# Radio_Console-AS_ORDERED_2015-05-06.net
KiCad netlist of a schematic drawn in EAGLE
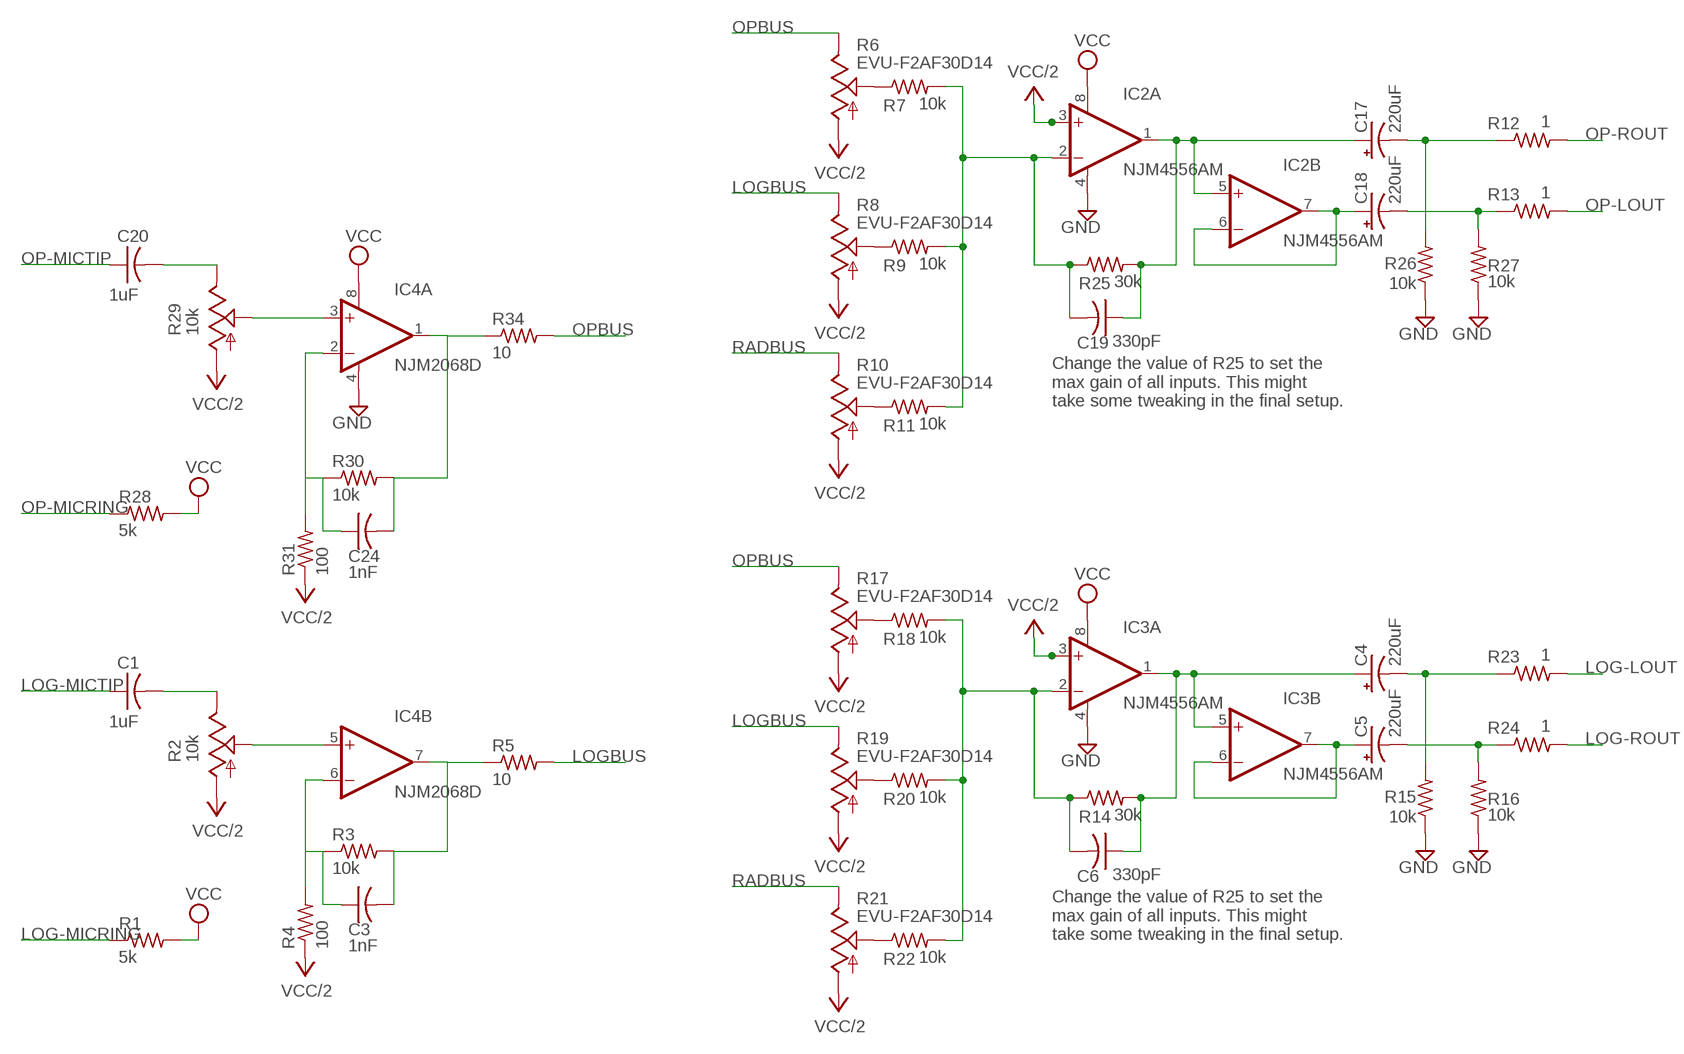
[diagram p0: schematic, sheet 1]
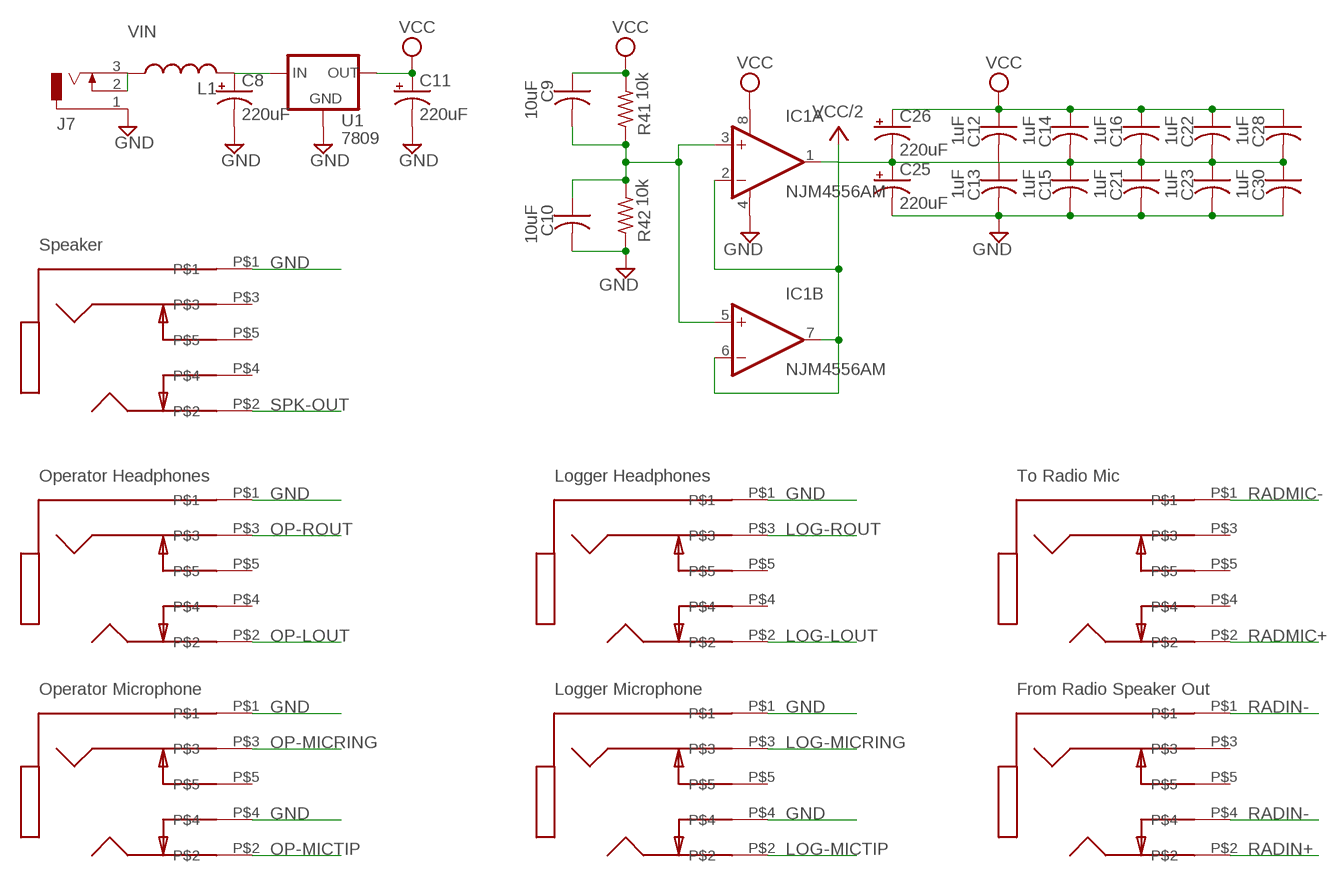
[diagram p1: schematic, sheet 2]
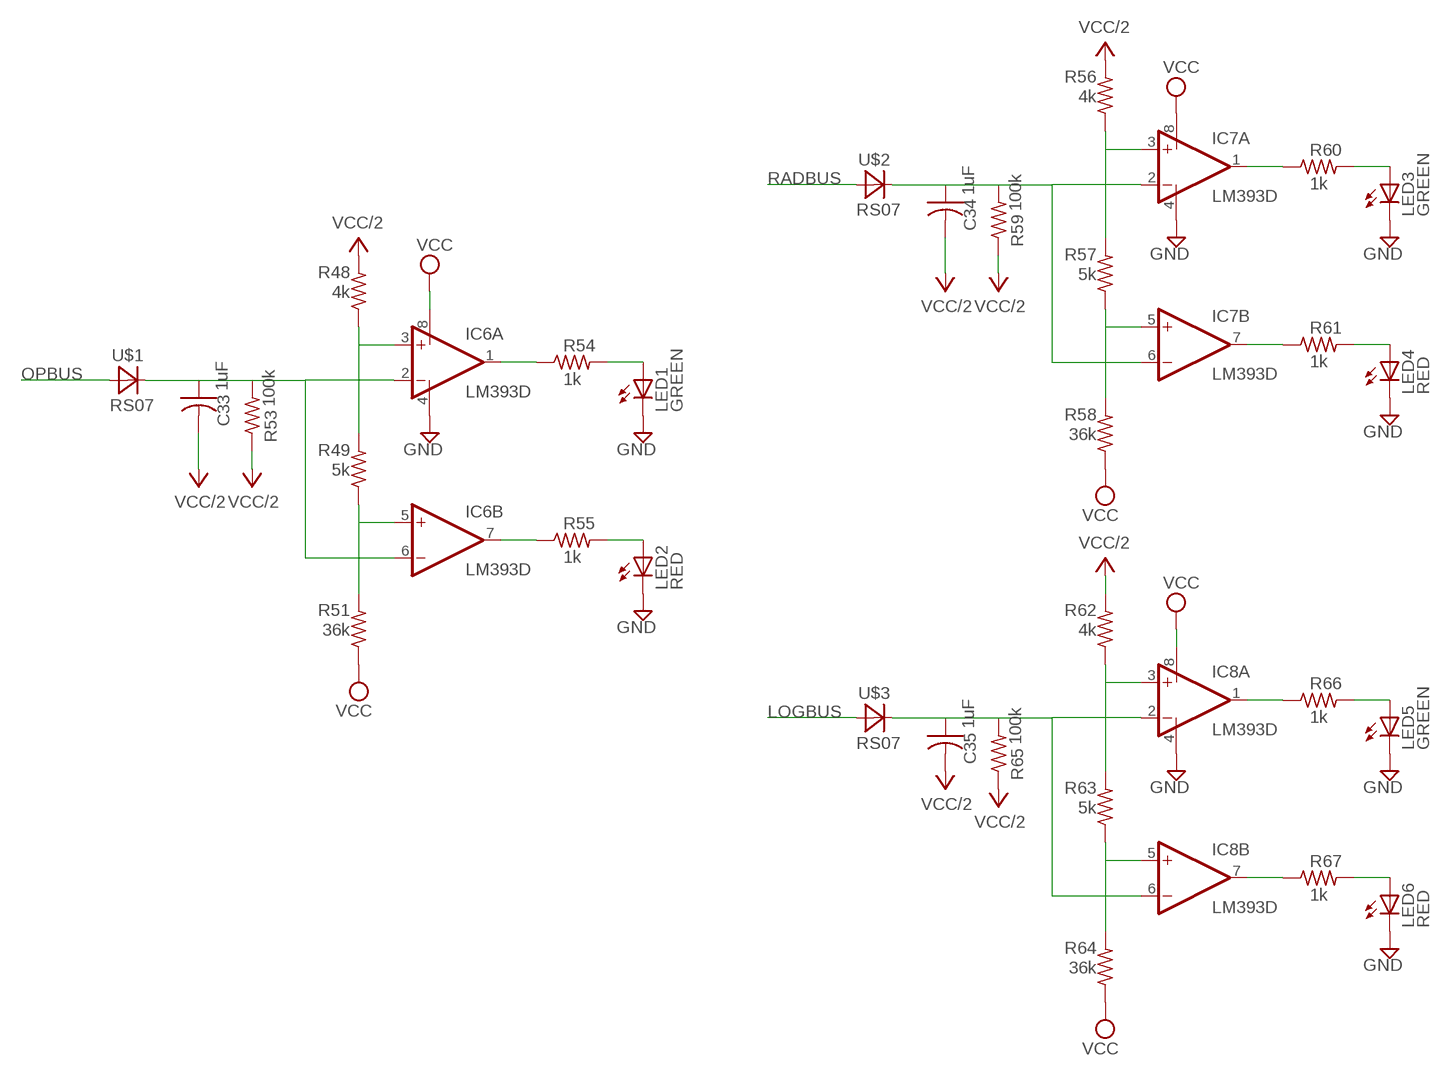
[diagram p2: schematic, sheet 3]
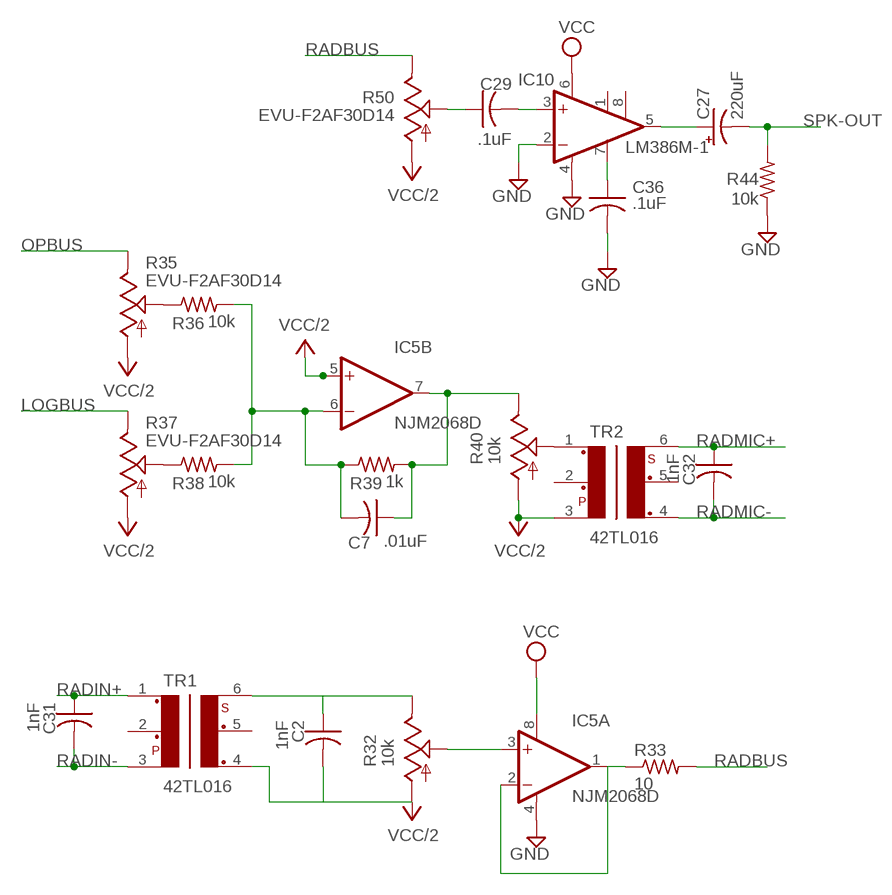
[diagram p3: schematic, sheet 4]

(export (version "E")
  (design (tool "Eeschema 10.0.6"))
  (components
    (comp (ref "C8")
      (value "220uF")
      (footprint "eagle-import:E5-8,5")
      (libsource (lib "eagle-import") (part "CPOL-USE5-8.5"))
    )
    (comp (ref "C9")
      (value "10uF")
      (footprint "eagle-import:C1206")
      (libsource (lib "eagle-import") (part "C-USC1206"))
    )
    (comp (ref "C10")
      (value "10uF")
      (footprint "eagle-import:C1206")
      (libsource (lib "eagle-import") (part "C-USC1206"))
    )
    (comp (ref "C11")
      (value "220uF")
      (footprint "eagle-import:E5-8,5")
      (libsource (lib "eagle-import") (part "CPOL-USE5-8.5"))
    )
    (comp (ref "C12")
      (value "1uF")
      (footprint "eagle-import:C1206")
      (libsource (lib "eagle-import") (part "C-USC1206"))
    )
    (comp (ref "C13")
      (value "1uF")
      (footprint "eagle-import:C1206")
      (libsource (lib "eagle-import") (part "C-USC1206"))
    )
    (comp (ref "C14")
      (value "1uF")
      (footprint "eagle-import:C1206")
      (libsource (lib "eagle-import") (part "C-USC1206"))
    )
    (comp (ref "C15")
      (value "1uF")
      (footprint "eagle-import:C1206")
      (libsource (lib "eagle-import") (part "C-USC1206"))
    )
    (comp (ref "C16")
      (value "1uF")
      (footprint "eagle-import:C1206")
      (libsource (lib "eagle-import") (part "C-USC1206"))
    )
    (comp (ref "C21")
      (value "1uF")
      (footprint "eagle-import:C1206")
      (libsource (lib "eagle-import") (part "C-USC1206"))
    )
    (comp (ref "C22")
      (value "1uF")
      (footprint "eagle-import:C1206")
      (libsource (lib "eagle-import") (part "C-USC1206"))
    )
    (comp (ref "C23")
      (value "1uF")
      (footprint "eagle-import:C1206")
      (libsource (lib "eagle-import") (part "C-USC1206"))
    )
    (comp (ref "C25")
      (value "220uF")
      (footprint "eagle-import:E5-8,5")
      (libsource (lib "eagle-import") (part "CPOL-USE5-8.5"))
    )
    (comp (ref "C26")
      (value "220uF")
      (footprint "eagle-import:E5-8,5")
      (libsource (lib "eagle-import") (part "CPOL-USE5-8.5"))
    )
    (comp (ref "C28")
      (value "1uF")
      (footprint "eagle-import:C1206")
      (libsource (lib "eagle-import") (part "C-USC1206"))
    )
    (comp (ref "C30")
      (value "1uF")
      (footprint "eagle-import:C1206")
      (libsource (lib "eagle-import") (part "C-USC1206"))
    )
    (comp (ref "IC1")
      (value "NJM4556AM")
      (footprint "eagle-import:SO08")
      (fields (field (name "MF") "TEXAS INSTRUMENT CONNECTORS") (field (name "MPN") "OPA2131UJ/2K5"))
      (libsource (lib "eagle-import") (part "OPA2131U"))
    )
    (comp (ref "J1")
      (value "Operator Headphones")
      (footprint "eagle-import:SJ1-353")
      (libsource (lib "eagle-import") (part "SJ1-353"))
    )
    (comp (ref "J2")
      (value "Operator Microphone")
      (footprint "eagle-import:SJ1-353")
      (libsource (lib "eagle-import") (part "SJ1-353"))
    )
    (comp (ref "J3")
      (value "To Radio MIcrophone")
      (footprint "eagle-import:SJ1-353")
      (libsource (lib "eagle-import") (part "SJ1-353"))
    )
    (comp (ref "J4")
      (value "Logger Headphone")
      (footprint "eagle-import:SJ1-353")
      (libsource (lib "eagle-import") (part "SJ1-353"))
    )
    (comp (ref "J5")
      (value "Logger Microphone")
      (footprint "eagle-import:SJ1-353")
      (libsource (lib "eagle-import") (part "SJ1-353"))
    )
    (comp (ref "J6")
      (value "From Radio Speaker Out")
      (footprint "eagle-import:SJ1-353")
      (libsource (lib "eagle-import") (part "SJ1-353"))
    )
    (comp (ref "J7")
      (value "DCJ0303")
      (footprint "eagle-import:DCJ0303")
      (libsource (lib "eagle-import") (part "DCJ0303"))
    )
    (comp (ref "J8")
      (value "Operator Headphones")
      (footprint "eagle-import:SJ1-353")
      (libsource (lib "eagle-import") (part "SJ1-353"))
    )
    (comp (ref "L1")
      (value "L-USL4035M")
      (footprint "eagle-import:L4035M")
      (libsource (lib "eagle-import") (part "L-USL4035M"))
    )
    (comp (ref "R41")
      (value "10k")
      (footprint "eagle-import:R1206")
      (libsource (lib "eagle-import") (part "R-US_R1206"))
    )
    (comp (ref "R42")
      (value "10k")
      (footprint "eagle-import:R1206")
      (libsource (lib "eagle-import") (part "R-US_R1206"))
    )
    (comp (ref "U1")
      (value "7809")
      (footprint "eagle-import:D2PACK")
      (libsource (lib "eagle-import") (part "78XX-TO263"))
    )
    (comp (ref "C33")
      (value "1uF")
      (footprint "eagle-import:C1206")
      (libsource (lib "eagle-import") (part "C-USC1206"))
    )
    (comp (ref "C34")
      (value "1uF")
      (footprint "eagle-import:C1206")
      (libsource (lib "eagle-import") (part "C-USC1206"))
    )
    (comp (ref "C35")
      (value "1uF")
      (footprint "eagle-import:C1206")
      (libsource (lib "eagle-import") (part "C-USC1206"))
    )
    (comp (ref "IC6")
      (value "LM393D")
      (footprint "eagle-import:SO08")
      (libsource (lib "eagle-import") (part "LM393D"))
    )
    (comp (ref "IC7")
      (value "LM393D")
      (footprint "eagle-import:SO08")
      (libsource (lib "eagle-import") (part "LM393D"))
    )
    (comp (ref "IC8")
      (value "LM393D")
      (footprint "eagle-import:SO08")
      (libsource (lib "eagle-import") (part "LM393D"))
    )
    (comp (ref "LED1")
      (value "GREEN")
      (footprint "eagle-import:LED3MM")
      (libsource (lib "eagle-import") (part "LED3MM"))
    )
    (comp (ref "LED2")
      (value "RED")
      (footprint "eagle-import:LED3MM")
      (libsource (lib "eagle-import") (part "LED3MM"))
    )
    (comp (ref "LED3")
      (value "GREEN")
      (footprint "eagle-import:LED3MM")
      (libsource (lib "eagle-import") (part "LED3MM"))
    )
    (comp (ref "LED4")
      (value "RED")
      (footprint "eagle-import:LED3MM")
      (libsource (lib "eagle-import") (part "LED3MM"))
    )
    (comp (ref "LED5")
      (value "GREEN")
      (footprint "eagle-import:LED3MM")
      (libsource (lib "eagle-import") (part "LED3MM"))
    )
    (comp (ref "LED6")
      (value "RED")
      (footprint "eagle-import:LED3MM")
      (libsource (lib "eagle-import") (part "LED3MM"))
    )
    (comp (ref "R48")
      (value "4k")
      (footprint "eagle-import:R1206")
      (libsource (lib "eagle-import") (part "R-US_R1206"))
    )
    (comp (ref "R49")
      (value "5k")
      (footprint "eagle-import:R1206")
      (libsource (lib "eagle-import") (part "R-US_R1206"))
    )
    (comp (ref "R51")
      (value "36k")
      (footprint "eagle-import:R1206")
      (libsource (lib "eagle-import") (part "R-US_R1206"))
    )
    (comp (ref "R53")
      (value "100k")
      (footprint "eagle-import:R1206")
      (libsource (lib "eagle-import") (part "R-US_R1206"))
    )
    (comp (ref "R54")
      (value "1k")
      (footprint "eagle-import:R1206")
      (libsource (lib "eagle-import") (part "R-US_R1206"))
    )
    (comp (ref "R55")
      (value "1k")
      (footprint "eagle-import:R1206")
      (libsource (lib "eagle-import") (part "R-US_R1206"))
    )
    (comp (ref "R56")
      (value "4k")
      (footprint "eagle-import:R1206")
      (libsource (lib "eagle-import") (part "R-US_R1206"))
    )
    (comp (ref "R57")
      (value "5k")
      (footprint "eagle-import:R1206")
      (libsource (lib "eagle-import") (part "R-US_R1206"))
    )
    (comp (ref "R58")
      (value "36k")
      (footprint "eagle-import:R1206")
      (libsource (lib "eagle-import") (part "R-US_R1206"))
    )
    (comp (ref "R59")
      (value "100k")
      (footprint "eagle-import:R1206")
      (libsource (lib "eagle-import") (part "R-US_R1206"))
    )
    (comp (ref "R60")
      (value "1k")
      (footprint "eagle-import:R1206")
      (libsource (lib "eagle-import") (part "R-US_R1206"))
    )
    (comp (ref "R61")
      (value "1k")
      (footprint "eagle-import:R1206")
      (libsource (lib "eagle-import") (part "R-US_R1206"))
    )
    (comp (ref "R62")
      (value "4k")
      (footprint "eagle-import:R1206")
      (libsource (lib "eagle-import") (part "R-US_R1206"))
    )
    (comp (ref "R63")
      (value "5k")
      (footprint "eagle-import:R1206")
      (libsource (lib "eagle-import") (part "R-US_R1206"))
    )
    (comp (ref "R64")
      (value "36k")
      (footprint "eagle-import:R1206")
      (libsource (lib "eagle-import") (part "R-US_R1206"))
    )
    (comp (ref "R65")
      (value "100k")
      (footprint "eagle-import:R1206")
      (libsource (lib "eagle-import") (part "R-US_R1206"))
    )
    (comp (ref "R66")
      (value "1k")
      (footprint "eagle-import:R1206")
      (libsource (lib "eagle-import") (part "R-US_R1206"))
    )
    (comp (ref "R67")
      (value "1k")
      (footprint "eagle-import:R1206")
      (libsource (lib "eagle-import") (part "R-US_R1206"))
    )
    (comp (ref "U$1")
      (value "RS07")
      (footprint "eagle-import:DO-219AB")
      (libsource (lib "eagle-import") (part "RS07"))
    )
    (comp (ref "U$2")
      (value "RS07")
      (footprint "eagle-import:DO-219AB")
      (libsource (lib "eagle-import") (part "RS07"))
    )
    (comp (ref "U$3")
      (value "RS07")
      (footprint "eagle-import:DO-219AB")
      (libsource (lib "eagle-import") (part "RS07"))
    )
    (comp (ref "C2")
      (value "1nF")
      (footprint "eagle-import:C1206")
      (libsource (lib "eagle-import") (part "C-USC1206"))
    )
    (comp (ref "C7")
      (value ".01uF")
      (footprint "eagle-import:C1206")
      (libsource (lib "eagle-import") (part "C-USC1206"))
    )
    (comp (ref "C27")
      (value "220uF")
      (footprint "eagle-import:E5-8,5")
      (libsource (lib "eagle-import") (part "CPOL-USE5-8.5"))
    )
    (comp (ref "C29")
      (value ".1uF")
      (footprint "eagle-import:C1206")
      (libsource (lib "eagle-import") (part "C-USC1206"))
    )
    (comp (ref "C31")
      (value "1nF")
      (footprint "eagle-import:C1206")
      (libsource (lib "eagle-import") (part "C-USC1206"))
    )
    (comp (ref "C32")
      (value "1nF")
      (footprint "eagle-import:C1206")
      (libsource (lib "eagle-import") (part "C-USC1206"))
    )
    (comp (ref "C36")
      (value ".1uF")
      (footprint "eagle-import:C1206")
      (libsource (lib "eagle-import") (part "C-USC1206"))
    )
    (comp (ref "IC5")
      (value "NJM2068D")
      (footprint "eagle-import:SO08")
      (fields (field (name "MF") "TEXAS INSTRUMENT CONNECTORS") (field (name "MPN") "OPA2131UJ/2K5"))
      (libsource (lib "eagle-import") (part "OPA2131U"))
    )
    (comp (ref "IC10")
      (value "LM386M-1")
      (footprint "eagle-import:SO08")
      (libsource (lib "eagle-import") (part "LM386?-M1"))
    )
    (comp (ref "R32")
      (value "10k")
      (footprint "eagle-import:S64W")
      (libsource (lib "eagle-import") (part "TRIM_US-S64W"))
    )
    (comp (ref "R33")
      (value "10")
      (footprint "eagle-import:R1206")
      (libsource (lib "eagle-import") (part "R-US_R1206"))
    )
    (comp (ref "R35")
      (value "EVU-F2AF30D14")
      (footprint "eagle-import:EVUFXM")
      (libsource (lib "eagle-import") (part "US-EVUMF2"))
    )
    (comp (ref "R36")
      (value "10k")
      (footprint "eagle-import:R1206")
      (libsource (lib "eagle-import") (part "R-US_R1206"))
    )
    (comp (ref "R37")
      (value "EVU-F2AF30D14")
      (footprint "eagle-import:EVUFXM")
      (libsource (lib "eagle-import") (part "US-EVUMF2"))
    )
    (comp (ref "R38")
      (value "10k")
      (footprint "eagle-import:R1206")
      (libsource (lib "eagle-import") (part "R-US_R1206"))
    )
    (comp (ref "R39")
      (value "1k")
      (footprint "eagle-import:R1206")
      (libsource (lib "eagle-import") (part "R-US_R1206"))
    )
    (comp (ref "R40")
      (value "10k")
      (footprint "eagle-import:S64W")
      (libsource (lib "eagle-import") (part "TRIM_US-S64W"))
    )
    (comp (ref "R44")
      (value "10k")
      (footprint "eagle-import:R1206")
      (libsource (lib "eagle-import") (part "R-US_R1206"))
    )
    (comp (ref "R50")
      (value "EVU-F2AF30D14")
      (footprint "eagle-import:EVUFXM")
      (libsource (lib "eagle-import") (part "US-EVUMF2"))
    )
    (comp (ref "TR1")
      (value "42TL016")
      (footprint "eagle-import:42TL")
      (libsource (lib "eagle-import") (part "42T?L016"))
    )
    (comp (ref "TR2")
      (value "42TL016")
      (footprint "eagle-import:42TL")
      (libsource (lib "eagle-import") (part "42T?L016"))
    )
    (comp (ref "C1")
      (value "1uF")
      (footprint "eagle-import:C1206")
      (libsource (lib "eagle-import") (part "C-USC1206"))
    )
    (comp (ref "C3")
      (value "1nF")
      (footprint "eagle-import:C1206")
      (libsource (lib "eagle-import") (part "C-USC1206"))
    )
    (comp (ref "C4")
      (value "220uF")
      (footprint "eagle-import:E5-8,5")
      (libsource (lib "eagle-import") (part "CPOL-USE5-8.5"))
    )
    (comp (ref "C5")
      (value "220uF")
      (footprint "eagle-import:E5-8,5")
      (libsource (lib "eagle-import") (part "CPOL-USE5-8.5"))
    )
    (comp (ref "C6")
      (value "330pF")
      (footprint "eagle-import:C1206")
      (libsource (lib "eagle-import") (part "C-USC1206"))
    )
    (comp (ref "C17")
      (value "220uF")
      (footprint "eagle-import:E5-8,5")
      (libsource (lib "eagle-import") (part "CPOL-USE5-8.5"))
    )
    (comp (ref "C18")
      (value "220uF")
      (footprint "eagle-import:E5-8,5")
      (libsource (lib "eagle-import") (part "CPOL-USE5-8.5"))
    )
    (comp (ref "C19")
      (value "330pF")
      (footprint "eagle-import:C1206")
      (libsource (lib "eagle-import") (part "C-USC1206"))
    )
    (comp (ref "C20")
      (value "1uF")
      (footprint "eagle-import:C1206")
      (libsource (lib "eagle-import") (part "C-USC1206"))
    )
    (comp (ref "C24")
      (value "1nF")
      (footprint "eagle-import:C1206")
      (libsource (lib "eagle-import") (part "C-USC1206"))
    )
    (comp (ref "IC2")
      (value "NJM4556AM")
      (footprint "eagle-import:SO08")
      (fields (field (name "MF") "TEXAS INSTRUMENT CONNECTORS") (field (name "MPN") "OPA2131UJ/2K5"))
      (libsource (lib "eagle-import") (part "OPA2131U"))
    )
    (comp (ref "IC3")
      (value "NJM4556AM")
      (footprint "eagle-import:SO08")
      (fields (field (name "MF") "TEXAS INSTRUMENT CONNECTORS") (field (name "MPN") "OPA2131UJ/2K5"))
      (libsource (lib "eagle-import") (part "OPA2131U"))
    )
    (comp (ref "IC4")
      (value "NJM2068D")
      (footprint "eagle-import:SO08")
      (fields (field (name "MF") "TEXAS INSTRUMENT CONNECTORS") (field (name "MPN") "OPA2131UJ/2K5"))
      (libsource (lib "eagle-import") (part "OPA2131U"))
    )
    (comp (ref "R1")
      (value "5k")
      (footprint "eagle-import:R1206")
      (libsource (lib "eagle-import") (part "R-US_R1206"))
    )
    (comp (ref "R2")
      (value "10k")
      (footprint "eagle-import:S64W")
      (libsource (lib "eagle-import") (part "TRIM_US-S64W"))
    )
    (comp (ref "R3")
      (value "10k")
      (footprint "eagle-import:R1206")
      (libsource (lib "eagle-import") (part "R-US_R1206"))
    )
    (comp (ref "R4")
      (value "100")
      (footprint "eagle-import:R1206")
      (libsource (lib "eagle-import") (part "R-US_R1206"))
    )
    (comp (ref "R5")
      (value "10")
      (footprint "eagle-import:R1206")
      (libsource (lib "eagle-import") (part "R-US_R1206"))
    )
    (comp (ref "R6")
      (value "EVU-F2AF30D14")
      (footprint "eagle-import:EVUFXM")
      (libsource (lib "eagle-import") (part "US-EVUMF2"))
    )
    (comp (ref "R7")
      (value "10k")
      (footprint "eagle-import:R1206")
      (libsource (lib "eagle-import") (part "R-US_R1206"))
    )
    (comp (ref "R8")
      (value "EVU-F2AF30D14")
      (footprint "eagle-import:EVUFXM")
      (libsource (lib "eagle-import") (part "US-EVUMF2"))
    )
    (comp (ref "R9")
      (value "10k")
      (footprint "eagle-import:R1206")
      (libsource (lib "eagle-import") (part "R-US_R1206"))
    )
    (comp (ref "R10")
      (value "EVU-F2AF30D14")
      (footprint "eagle-import:EVUFXM")
      (libsource (lib "eagle-import") (part "US-EVUMF2"))
    )
    (comp (ref "R11")
      (value "10k")
      (footprint "eagle-import:R1206")
      (libsource (lib "eagle-import") (part "R-US_R1206"))
    )
    (comp (ref "R12")
      (value "1")
      (footprint "eagle-import:R1206")
      (libsource (lib "eagle-import") (part "R-US_R1206"))
    )
    (comp (ref "R13")
      (value "1")
      (footprint "eagle-import:R1206")
      (libsource (lib "eagle-import") (part "R-US_R1206"))
    )
    (comp (ref "R14")
      (value "30k")
      (footprint "eagle-import:R1206")
      (libsource (lib "eagle-import") (part "R-US_R1206"))
    )
    (comp (ref "R15")
      (value "10k")
      (footprint "eagle-import:R1206")
      (libsource (lib "eagle-import") (part "R-US_R1206"))
    )
    (comp (ref "R16")
      (value "10k")
      (footprint "eagle-import:R1206")
      (libsource (lib "eagle-import") (part "R-US_R1206"))
    )
    (comp (ref "R17")
      (value "EVU-F2AF30D14")
      (footprint "eagle-import:EVUFXM")
      (libsource (lib "eagle-import") (part "US-EVUMF2"))
    )
    (comp (ref "R18")
      (value "10k")
      (footprint "eagle-import:R1206")
      (libsource (lib "eagle-import") (part "R-US_R1206"))
    )
    (comp (ref "R19")
      (value "EVU-F2AF30D14")
      (footprint "eagle-import:EVUFXM")
      (libsource (lib "eagle-import") (part "US-EVUMF2"))
    )
    (comp (ref "R20")
      (value "10k")
      (footprint "eagle-import:R1206")
      (libsource (lib "eagle-import") (part "R-US_R1206"))
    )
    (comp (ref "R21")
      (value "EVU-F2AF30D14")
      (footprint "eagle-import:EVUFXM")
      (libsource (lib "eagle-import") (part "US-EVUMF2"))
    )
    (comp (ref "R22")
      (value "10k")
      (footprint "eagle-import:R1206")
      (libsource (lib "eagle-import") (part "R-US_R1206"))
    )
    (comp (ref "R23")
      (value "1")
      (footprint "eagle-import:R1206")
      (libsource (lib "eagle-import") (part "R-US_R1206"))
    )
    (comp (ref "R24")
      (value "1")
      (footprint "eagle-import:R1206")
      (libsource (lib "eagle-import") (part "R-US_R1206"))
    )
    (comp (ref "R25")
      (value "30k")
      (footprint "eagle-import:R1206")
      (libsource (lib "eagle-import") (part "R-US_R1206"))
    )
    (comp (ref "R26")
      (value "10k")
      (footprint "eagle-import:R1206")
      (libsource (lib "eagle-import") (part "R-US_R1206"))
    )
    (comp (ref "R27")
      (value "10k")
      (footprint "eagle-import:R1206")
      (libsource (lib "eagle-import") (part "R-US_R1206"))
    )
    (comp (ref "R28")
      (value "5k")
      (footprint "eagle-import:R1206")
      (libsource (lib "eagle-import") (part "R-US_R1206"))
    )
    (comp (ref "R29")
      (value "10k")
      (footprint "eagle-import:S64W")
      (libsource (lib "eagle-import") (part "TRIM_US-S64W"))
    )
    (comp (ref "R30")
      (value "10k")
      (footprint "eagle-import:R1206")
      (libsource (lib "eagle-import") (part "R-US_R1206"))
    )
    (comp (ref "R31")
      (value "100")
      (footprint "eagle-import:R1206")
      (libsource (lib "eagle-import") (part "R-US_R1206"))
    )
    (comp (ref "R34")
      (value "10")
      (footprint "eagle-import:R1206")
      (libsource (lib "eagle-import") (part "R-US_R1206"))
    )
  )
  (nets
    (net (code "1") (name "GND") (class "Default")
      (node (ref "C10") (pin "2") (pinfunction "2_2") (pintype "passive"))
      (node (ref "C11") (pin "-") (pinfunction "-_-") (pintype "passive"))
      (node (ref "C13") (pin "2") (pinfunction "2_2") (pintype "passive"))
      (node (ref "C15") (pin "2") (pinfunction "2_2") (pintype "passive"))
      (node (ref "C21") (pin "2") (pinfunction "2_2") (pintype "passive"))
      (node (ref "C23") (pin "2") (pinfunction "2_2") (pintype "passive"))
      (node (ref "C25") (pin "-") (pinfunction "-_-") (pintype "passive"))
      (node (ref "C30") (pin "2") (pinfunction "2_2") (pintype "passive"))
      (node (ref "C36") (pin "2") (pinfunction "2_2") (pintype "passive"))
      (node (ref "C8") (pin "-") (pinfunction "-_-") (pintype "passive"))
      (node (ref "IC1") (pin "4") (pinfunction "V-_4") (pintype "power_in"))
      (node (ref "IC10") (pin "2") (pinfunction "-IN_2") (pintype "input"))
      (node (ref "IC10") (pin "4") (pinfunction "GND_4") (pintype "power_in"))
      (node (ref "IC2") (pin "4") (pinfunction "V-_4") (pintype "power_in"))
      (node (ref "IC3") (pin "4") (pinfunction "V-_4") (pintype "power_in"))
      (node (ref "IC4") (pin "4") (pinfunction "V-_4") (pintype "power_in"))
      (node (ref "IC5") (pin "4") (pinfunction "V-_4") (pintype "power_in"))
      (node (ref "IC6") (pin "4") (pinfunction "V-_4") (pintype "power_in"))
      (node (ref "IC7") (pin "4") (pinfunction "V-_4") (pintype "power_in"))
      (node (ref "IC8") (pin "4") (pinfunction "V-_4") (pintype "power_in"))
      (node (ref "J1") (pin "P$1") (pinfunction "P$1_P$1") (pintype "bidirectional"))
      (node (ref "J2") (pin "P$1") (pinfunction "P$1_P$1") (pintype "bidirectional"))
      (node (ref "J2") (pin "P$4") (pinfunction "P$4_P$4") (pintype "bidirectional"))
      (node (ref "J4") (pin "P$1") (pinfunction "P$1_P$1") (pintype "bidirectional"))
      (node (ref "J5") (pin "P$1") (pinfunction "P$1_P$1") (pintype "bidirectional"))
      (node (ref "J5") (pin "P$4") (pinfunction "P$4_P$4") (pintype "bidirectional"))
      (node (ref "J7") (pin "1") (pinfunction "1_1") (pintype "passive"))
      (node (ref "J8") (pin "P$1") (pinfunction "P$1_P$1") (pintype "bidirectional"))
      (node (ref "LED1") (pin "K") (pinfunction "C_K") (pintype "passive"))
      (node (ref "LED2") (pin "K") (pinfunction "C_K") (pintype "passive"))
      (node (ref "LED3") (pin "K") (pinfunction "C_K") (pintype "passive"))
      (node (ref "LED4") (pin "K") (pinfunction "C_K") (pintype "passive"))
      (node (ref "LED5") (pin "K") (pinfunction "C_K") (pintype "passive"))
      (node (ref "LED6") (pin "K") (pinfunction "C_K") (pintype "passive"))
      (node (ref "R15") (pin "1") (pinfunction "1_1") (pintype "passive"))
      (node (ref "R16") (pin "1") (pinfunction "1_1") (pintype "passive"))
      (node (ref "R26") (pin "1") (pinfunction "1_1") (pintype "passive"))
      (node (ref "R27") (pin "1") (pinfunction "1_1") (pintype "passive"))
      (node (ref "R42") (pin "1") (pinfunction "1_1") (pintype "passive"))
      (node (ref "R44") (pin "1") (pinfunction "1_1") (pintype "passive"))
      (node (ref "U1") (pin "2") (pinfunction "GND_2") (pintype "input"))
    )
    (net (code "2") (name "LOG-LOUT") (class "Default")
      (node (ref "J4") (pin "P$2") (pinfunction "P$2_P$2") (pintype "bidirectional"))
      (node (ref "R23") (pin "2") (pinfunction "2_2") (pintype "passive"))
    )
    (net (code "3") (name "LOG-MICRING") (class "Default")
      (node (ref "J5") (pin "P$3") (pinfunction "P$3_P$3") (pintype "bidirectional"))
      (node (ref "R1") (pin "1") (pinfunction "1_1") (pintype "passive"))
    )
    (net (code "4") (name "LOG-MICTIP") (class "Default")
      (node (ref "C1") (pin "1") (pinfunction "1_1") (pintype "passive"))
      (node (ref "J5") (pin "P$2") (pinfunction "P$2_P$2") (pintype "bidirectional"))
    )
    (net (code "5") (name "LOG-ROUT") (class "Default")
      (node (ref "J4") (pin "P$3") (pinfunction "P$3_P$3") (pintype "bidirectional"))
      (node (ref "R24") (pin "2") (pinfunction "2_2") (pintype "passive"))
    )
    (net (code "6") (name "LOGBUS") (class "Default")
      (node (ref "R19") (pin "3") (pinfunction "E_3") (pintype "passive"))
      (node (ref "R37") (pin "3") (pinfunction "E_3") (pintype "passive"))
      (node (ref "R5") (pin "2") (pinfunction "2_2") (pintype "passive"))
      (node (ref "R8") (pin "3") (pinfunction "E_3") (pintype "passive"))
      (node (ref "U$3") (pin "ANODE") (pinfunction "A_ANODE") (pintype "passive"))
    )
    (net (code "7") (name "Net-(C1-Pad2)") (class "Default")
      (node (ref "C1") (pin "2") (pinfunction "2_2") (pintype "passive"))
      (node (ref "R2") (pin "E") (pinfunction "E_E") (pintype "passive"))
    )
    (net (code "8") (name "Net-(C2-Pad1)") (class "Default")
      (node (ref "C2") (pin "1") (pinfunction "1_1") (pintype "passive"))
      (node (ref "R32") (pin "E") (pinfunction "E_E") (pintype "passive"))
      (node (ref "TR1") (pin "6") (pinfunction "6_6") (pintype "passive"))
    )
    (net (code "9") (name "Net-(C4-Pad-)") (class "Default")
      (node (ref "C4") (pin "-") (pinfunction "-_-") (pintype "passive"))
      (node (ref "R15") (pin "2") (pinfunction "2_2") (pintype "passive"))
      (node (ref "R23") (pin "1") (pinfunction "1_1") (pintype "passive"))
    )
    (net (code "10") (name "Net-(C5-Pad-)") (class "Default")
      (node (ref "C5") (pin "-") (pinfunction "-_-") (pintype "passive"))
      (node (ref "R16") (pin "2") (pinfunction "2_2") (pintype "passive"))
      (node (ref "R24") (pin "1") (pinfunction "1_1") (pintype "passive"))
    )
    (net (code "11") (name "Net-(C17-Pad-)") (class "Default")
      (node (ref "C17") (pin "-") (pinfunction "-_-") (pintype "passive"))
      (node (ref "R12") (pin "1") (pinfunction "1_1") (pintype "passive"))
      (node (ref "R26") (pin "2") (pinfunction "2_2") (pintype "passive"))
    )
    (net (code "12") (name "Net-(C18-Pad-)") (class "Default")
      (node (ref "C18") (pin "-") (pinfunction "-_-") (pintype "passive"))
      (node (ref "R13") (pin "1") (pinfunction "1_1") (pintype "passive"))
      (node (ref "R27") (pin "2") (pinfunction "2_2") (pintype "passive"))
    )
    (net (code "13") (name "Net-(C20-Pad2)") (class "Default")
      (node (ref "C20") (pin "2") (pinfunction "2_2") (pintype "passive"))
      (node (ref "R29") (pin "E") (pinfunction "E_E") (pintype "passive"))
    )
    (net (code "14") (name "Net-(IC1A-+IN)") (class "Default")
      (node (ref "C10") (pin "1") (pinfunction "1_1") (pintype "passive"))
      (node (ref "C9") (pin "2") (pinfunction "2_2") (pintype "passive"))
      (node (ref "IC1") (pin "3") (pinfunction "+IN_3") (pintype "input"))
      (node (ref "IC1") (pin "5") (pinfunction "+IN_5") (pintype "input"))
      (node (ref "R41") (pin "1") (pinfunction "1_1") (pintype "passive"))
      (node (ref "R42") (pin "2") (pinfunction "2_2") (pintype "passive"))
    )
    (net (code "15") (name "Net-(IC2A--IN)") (class "Default")
      (node (ref "C19") (pin "2") (pinfunction "2_2") (pintype "passive"))
      (node (ref "IC2") (pin "2") (pinfunction "-IN_2") (pintype "input"))
      (node (ref "R11") (pin "2") (pinfunction "2_2") (pintype "passive"))
      (node (ref "R25") (pin "1") (pinfunction "1_1") (pintype "passive"))
      (node (ref "R7") (pin "2") (pinfunction "2_2") (pintype "passive"))
      (node (ref "R9") (pin "2") (pinfunction "2_2") (pintype "passive"))
    )
    (net (code "16") (name "Net-(IC2A-OUT)") (class "Default")
      (node (ref "C17") (pin "+") (pinfunction "+_+") (pintype "passive"))
      (node (ref "C19") (pin "1") (pinfunction "1_1") (pintype "passive"))
      (node (ref "IC2") (pin "1") (pinfunction "OUT_1") (pintype "output"))
      (node (ref "IC2") (pin "5") (pinfunction "+IN_5") (pintype "input"))
      (node (ref "R25") (pin "2") (pinfunction "2_2") (pintype "passive"))
    )
    (net (code "17") (name "Net-(IC2B--IN)") (class "Default")
      (node (ref "C18") (pin "+") (pinfunction "+_+") (pintype "passive"))
      (node (ref "IC2") (pin "6") (pinfunction "-IN_6") (pintype "input"))
      (node (ref "IC2") (pin "7") (pinfunction "OUT_7") (pintype "output"))
    )
    (net (code "18") (name "Net-(IC3A--IN)") (class "Default")
      (node (ref "C6") (pin "2") (pinfunction "2_2") (pintype "passive"))
      (node (ref "IC3") (pin "2") (pinfunction "-IN_2") (pintype "input"))
      (node (ref "R14") (pin "1") (pinfunction "1_1") (pintype "passive"))
      (node (ref "R18") (pin "2") (pinfunction "2_2") (pintype "passive"))
      (node (ref "R20") (pin "2") (pinfunction "2_2") (pintype "passive"))
      (node (ref "R22") (pin "2") (pinfunction "2_2") (pintype "passive"))
    )
    (net (code "19") (name "Net-(IC3A-OUT)") (class "Default")
      (node (ref "C4") (pin "+") (pinfunction "+_+") (pintype "passive"))
      (node (ref "C6") (pin "1") (pinfunction "1_1") (pintype "passive"))
      (node (ref "IC3") (pin "1") (pinfunction "OUT_1") (pintype "output"))
      (node (ref "IC3") (pin "5") (pinfunction "+IN_5") (pintype "input"))
      (node (ref "R14") (pin "2") (pinfunction "2_2") (pintype "passive"))
    )
    (net (code "20") (name "Net-(IC3B--IN)") (class "Default")
      (node (ref "C5") (pin "+") (pinfunction "+_+") (pintype "passive"))
      (node (ref "IC3") (pin "6") (pinfunction "-IN_6") (pintype "input"))
      (node (ref "IC3") (pin "7") (pinfunction "OUT_7") (pintype "output"))
    )
    (net (code "21") (name "Net-(IC4A-+IN)") (class "Default")
      (node (ref "IC4") (pin "3") (pinfunction "+IN_3") (pintype "input"))
      (node (ref "R29") (pin "S") (pinfunction "S_S") (pintype "passive"))
    )
    (net (code "22") (name "Net-(IC4A--IN)") (class "Default")
      (node (ref "C24") (pin "1") (pinfunction "1_1") (pintype "passive"))
      (node (ref "IC4") (pin "2") (pinfunction "-IN_2") (pintype "input"))
      (node (ref "R30") (pin "1") (pinfunction "1_1") (pintype "passive"))
      (node (ref "R31") (pin "2") (pinfunction "2_2") (pintype "passive"))
    )
    (net (code "23") (name "Net-(IC4A-OUT)") (class "Default")
      (node (ref "C24") (pin "2") (pinfunction "2_2") (pintype "passive"))
      (node (ref "IC4") (pin "1") (pinfunction "OUT_1") (pintype "output"))
      (node (ref "R30") (pin "2") (pinfunction "2_2") (pintype "passive"))
      (node (ref "R34") (pin "1") (pinfunction "1_1") (pintype "passive"))
    )
    (net (code "24") (name "Net-(IC4B-+IN)") (class "Default")
      (node (ref "IC4") (pin "5") (pinfunction "+IN_5") (pintype "input"))
      (node (ref "R2") (pin "S") (pinfunction "S_S") (pintype "passive"))
    )
    (net (code "25") (name "Net-(IC4B--IN)") (class "Default")
      (node (ref "C3") (pin "1") (pinfunction "1_1") (pintype "passive"))
      (node (ref "IC4") (pin "6") (pinfunction "-IN_6") (pintype "input"))
      (node (ref "R3") (pin "1") (pinfunction "1_1") (pintype "passive"))
      (node (ref "R4") (pin "2") (pinfunction "2_2") (pintype "passive"))
    )
    (net (code "26") (name "Net-(IC4B-OUT)") (class "Default")
      (node (ref "C3") (pin "2") (pinfunction "2_2") (pintype "passive"))
      (node (ref "IC4") (pin "7") (pinfunction "OUT_7") (pintype "output"))
      (node (ref "R3") (pin "2") (pinfunction "2_2") (pintype "passive"))
      (node (ref "R5") (pin "1") (pinfunction "1_1") (pintype "passive"))
    )
    (net (code "27") (name "Net-(IC5A-+IN)") (class "Default")
      (node (ref "IC5") (pin "3") (pinfunction "+IN_3") (pintype "input"))
      (node (ref "R32") (pin "S") (pinfunction "S_S") (pintype "passive"))
    )
    (net (code "28") (name "Net-(IC5A--IN)") (class "Default")
      (node (ref "IC5") (pin "1") (pinfunction "OUT_1") (pintype "output"))
      (node (ref "IC5") (pin "2") (pinfunction "-IN_2") (pintype "input"))
      (node (ref "R33") (pin "1") (pinfunction "1_1") (pintype "passive"))
    )
    (net (code "29") (name "Net-(IC5B--IN)") (class "Default")
      (node (ref "C7") (pin "2") (pinfunction "2_2") (pintype "passive"))
      (node (ref "IC5") (pin "6") (pinfunction "-IN_6") (pintype "input"))
      (node (ref "R36") (pin "2") (pinfunction "2_2") (pintype "passive"))
      (node (ref "R38") (pin "2") (pinfunction "2_2") (pintype "passive"))
      (node (ref "R39") (pin "1") (pinfunction "1_1") (pintype "passive"))
    )
    (net (code "30") (name "Net-(IC5B-OUT)") (class "Default")
      (node (ref "C7") (pin "1") (pinfunction "1_1") (pintype "passive"))
      (node (ref "IC5") (pin "7") (pinfunction "OUT_7") (pintype "output"))
      (node (ref "R39") (pin "2") (pinfunction "2_2") (pintype "passive"))
      (node (ref "R40") (pin "E") (pinfunction "E_E") (pintype "passive"))
    )
    (net (code "31") (name "Net-(IC6A-+IN)") (class "Default")
      (node (ref "IC6") (pin "3") (pinfunction "+IN_3") (pintype "input"))
      (node (ref "R48") (pin "1") (pinfunction "1_1") (pintype "passive"))
      (node (ref "R49") (pin "2") (pinfunction "2_2") (pintype "passive"))
    )
    (net (code "32") (name "Net-(IC6A--IN)") (class "Default")
      (node (ref "C33") (pin "1") (pinfunction "1_1") (pintype "passive"))
      (node (ref "IC6") (pin "2") (pinfunction "-IN_2") (pintype "input"))
      (node (ref "IC6") (pin "6") (pinfunction "-IN_6") (pintype "input"))
      (node (ref "R53") (pin "2") (pinfunction "2_2") (pintype "passive"))
      (node (ref "U$1") (pin "CATHODE") (pinfunction "C_CATHODE") (pintype "passive"))
    )
    (net (code "33") (name "Net-(IC6A-OUT)") (class "Default")
      (node (ref "IC6") (pin "1") (pinfunction "OUT_1") (pintype "output"))
      (node (ref "R54") (pin "1") (pinfunction "1_1") (pintype "passive"))
    )
    (net (code "34") (name "Net-(IC6B-+IN)") (class "Default")
      (node (ref "IC6") (pin "5") (pinfunction "+IN_5") (pintype "input"))
      (node (ref "R49") (pin "1") (pinfunction "1_1") (pintype "passive"))
      (node (ref "R51") (pin "2") (pinfunction "2_2") (pintype "passive"))
    )
    (net (code "35") (name "Net-(IC6B-OUT)") (class "Default")
      (node (ref "IC6") (pin "7") (pinfunction "OUT_7") (pintype "output"))
      (node (ref "R55") (pin "1") (pinfunction "1_1") (pintype "passive"))
    )
    (net (code "36") (name "Net-(IC7A-+IN)") (class "Default")
      (node (ref "IC7") (pin "3") (pinfunction "+IN_3") (pintype "input"))
      (node (ref "R56") (pin "1") (pinfunction "1_1") (pintype "passive"))
      (node (ref "R57") (pin "2") (pinfunction "2_2") (pintype "passive"))
    )
    (net (code "37") (name "Net-(IC7A--IN)") (class "Default")
      (node (ref "C34") (pin "1") (pinfunction "1_1") (pintype "passive"))
      (node (ref "IC7") (pin "2") (pinfunction "-IN_2") (pintype "input"))
      (node (ref "IC7") (pin "6") (pinfunction "-IN_6") (pintype "input"))
      (node (ref "R59") (pin "2") (pinfunction "2_2") (pintype "passive"))
      (node (ref "U$2") (pin "CATHODE") (pinfunction "C_CATHODE") (pintype "passive"))
    )
    (net (code "38") (name "Net-(IC7A-OUT)") (class "Default")
      (node (ref "IC7") (pin "1") (pinfunction "OUT_1") (pintype "output"))
      (node (ref "R60") (pin "1") (pinfunction "1_1") (pintype "passive"))
    )
    (net (code "39") (name "Net-(IC7B-+IN)") (class "Default")
      (node (ref "IC7") (pin "5") (pinfunction "+IN_5") (pintype "input"))
      (node (ref "R57") (pin "1") (pinfunction "1_1") (pintype "passive"))
      (node (ref "R58") (pin "2") (pinfunction "2_2") (pintype "passive"))
    )
    (net (code "40") (name "Net-(IC7B-OUT)") (class "Default")
      (node (ref "IC7") (pin "7") (pinfunction "OUT_7") (pintype "output"))
      (node (ref "R61") (pin "1") (pinfunction "1_1") (pintype "passive"))
    )
    (net (code "41") (name "Net-(IC8A-+IN)") (class "Default")
      (node (ref "IC8") (pin "3") (pinfunction "+IN_3") (pintype "input"))
      (node (ref "R62") (pin "1") (pinfunction "1_1") (pintype "passive"))
      (node (ref "R63") (pin "2") (pinfunction "2_2") (pintype "passive"))
    )
    (net (code "42") (name "Net-(IC8A--IN)") (class "Default")
      (node (ref "C35") (pin "1") (pinfunction "1_1") (pintype "passive"))
      (node (ref "IC8") (pin "2") (pinfunction "-IN_2") (pintype "input"))
      (node (ref "IC8") (pin "6") (pinfunction "-IN_6") (pintype "input"))
      (node (ref "R65") (pin "2") (pinfunction "2_2") (pintype "passive"))
      (node (ref "U$3") (pin "CATHODE") (pinfunction "C_CATHODE") (pintype "passive"))
    )
    (net (code "43") (name "Net-(IC8A-OUT)") (class "Default")
      (node (ref "IC8") (pin "1") (pinfunction "OUT_1") (pintype "output"))
      (node (ref "R66") (pin "1") (pinfunction "1_1") (pintype "passive"))
    )
    (net (code "44") (name "Net-(IC8B-+IN)") (class "Default")
      (node (ref "IC8") (pin "5") (pinfunction "+IN_5") (pintype "input"))
      (node (ref "R63") (pin "1") (pinfunction "1_1") (pintype "passive"))
      (node (ref "R64") (pin "2") (pinfunction "2_2") (pintype "passive"))
    )
    (net (code "45") (name "Net-(IC8B-OUT)") (class "Default")
      (node (ref "IC8") (pin "7") (pinfunction "OUT_7") (pintype "output"))
      (node (ref "R67") (pin "1") (pinfunction "1_1") (pintype "passive"))
    )
    (net (code "46") (name "Net-(IC10-+IN)") (class "Default")
      (node (ref "C29") (pin "2") (pinfunction "2_2") (pintype "passive"))
      (node (ref "IC10") (pin "3") (pinfunction "+IN_3") (pintype "input"))
    )
    (net (code "47") (name "Net-(IC10-BYPASS)") (class "Default")
      (node (ref "C36") (pin "1") (pinfunction "1_1") (pintype "passive"))
      (node (ref "IC10") (pin "7") (pinfunction "BYPASS_7") (pintype "passive"))
    )
    (net (code "48") (name "Net-(IC10-OUT)") (class "Default")
      (node (ref "C27") (pin "+") (pinfunction "+_+") (pintype "passive"))
      (node (ref "IC10") (pin "5") (pinfunction "OUT_5") (pintype "output"))
    )
    (net (code "49") (name "Net-(LED1-PadA)") (class "Default")
      (node (ref "LED1") (pin "A") (pinfunction "A_A") (pintype "passive"))
      (node (ref "R54") (pin "2") (pinfunction "2_2") (pintype "passive"))
    )
    (net (code "50") (name "Net-(LED2-PadA)") (class "Default")
      (node (ref "LED2") (pin "A") (pinfunction "A_A") (pintype "passive"))
      (node (ref "R55") (pin "2") (pinfunction "2_2") (pintype "passive"))
    )
    (net (code "51") (name "Net-(LED3-PadA)") (class "Default")
      (node (ref "LED3") (pin "A") (pinfunction "A_A") (pintype "passive"))
      (node (ref "R60") (pin "2") (pinfunction "2_2") (pintype "passive"))
    )
    (net (code "52") (name "Net-(LED4-PadA)") (class "Default")
      (node (ref "LED4") (pin "A") (pinfunction "A_A") (pintype "passive"))
      (node (ref "R61") (pin "2") (pinfunction "2_2") (pintype "passive"))
    )
    (net (code "53") (name "Net-(LED5-PadA)") (class "Default")
      (node (ref "LED5") (pin "A") (pinfunction "A_A") (pintype "passive"))
      (node (ref "R66") (pin "2") (pinfunction "2_2") (pintype "passive"))
    )
    (net (code "54") (name "Net-(LED6-PadA)") (class "Default")
      (node (ref "LED6") (pin "A") (pinfunction "A_A") (pintype "passive"))
      (node (ref "R67") (pin "2") (pinfunction "2_2") (pintype "passive"))
    )
    (net (code "55") (name "Net-(R6-S)") (class "Default")
      (node (ref "R6") (pin "2") (pinfunction "S_2") (pintype "passive"))
      (node (ref "R7") (pin "1") (pinfunction "1_1") (pintype "passive"))
    )
    (net (code "56") (name "Net-(R8-S)") (class "Default")
      (node (ref "R8") (pin "2") (pinfunction "S_2") (pintype "passive"))
      (node (ref "R9") (pin "1") (pinfunction "1_1") (pintype "passive"))
    )
    (net (code "57") (name "Net-(R10-S)") (class "Default")
      (node (ref "R10") (pin "2") (pinfunction "S_2") (pintype "passive"))
      (node (ref "R11") (pin "1") (pinfunction "1_1") (pintype "passive"))
    )
    (net (code "58") (name "Net-(R17-S)") (class "Default")
      (node (ref "R17") (pin "2") (pinfunction "S_2") (pintype "passive"))
      (node (ref "R18") (pin "1") (pinfunction "1_1") (pintype "passive"))
    )
    (net (code "59") (name "Net-(R19-S)") (class "Default")
      (node (ref "R19") (pin "2") (pinfunction "S_2") (pintype "passive"))
      (node (ref "R20") (pin "1") (pinfunction "1_1") (pintype "passive"))
    )
    (net (code "60") (name "Net-(R21-S)") (class "Default")
      (node (ref "R21") (pin "2") (pinfunction "S_2") (pintype "passive"))
      (node (ref "R22") (pin "1") (pinfunction "1_1") (pintype "passive"))
    )
    (net (code "61") (name "Net-(R35-S)") (class "Default")
      (node (ref "R35") (pin "2") (pinfunction "S_2") (pintype "passive"))
      (node (ref "R36") (pin "1") (pinfunction "1_1") (pintype "passive"))
    )
    (net (code "62") (name "Net-(R37-S)") (class "Default")
      (node (ref "R37") (pin "2") (pinfunction "S_2") (pintype "passive"))
      (node (ref "R38") (pin "1") (pinfunction "1_1") (pintype "passive"))
    )
    (net (code "63") (name "Net-(R40-PadS)") (class "Default")
      (node (ref "R40") (pin "S") (pinfunction "S_S") (pintype "passive"))
      (node (ref "TR2") (pin "1") (pinfunction "1_1") (pintype "passive"))
    )
    (net (code "64") (name "Net-(R50-S)") (class "Default")
      (node (ref "C29") (pin "1") (pinfunction "1_1") (pintype "passive"))
      (node (ref "R50") (pin "2") (pinfunction "S_2") (pintype "passive"))
    )
    (net (code "65") (name "Net-(U1-IN)") (class "Default")
      (node (ref "C8") (pin "+") (pinfunction "+_+") (pintype "passive"))
      (node (ref "L1") (pin "2") (pinfunction "2_2") (pintype "passive"))
      (node (ref "U1") (pin "1") (pinfunction "IN_1") (pintype "input"))
    )
    (net (code "66") (name "OP-LOUT") (class "Default")
      (node (ref "J1") (pin "P$2") (pinfunction "P$2_P$2") (pintype "bidirectional"))
      (node (ref "R13") (pin "2") (pinfunction "2_2") (pintype "passive"))
    )
    (net (code "67") (name "OP-MICRING") (class "Default")
      (node (ref "J2") (pin "P$3") (pinfunction "P$3_P$3") (pintype "bidirectional"))
      (node (ref "R28") (pin "1") (pinfunction "1_1") (pintype "passive"))
    )
    (net (code "68") (name "OP-MICTIP") (class "Default")
      (node (ref "C20") (pin "1") (pinfunction "1_1") (pintype "passive"))
      (node (ref "J2") (pin "P$2") (pinfunction "P$2_P$2") (pintype "bidirectional"))
    )
    (net (code "69") (name "OP-ROUT") (class "Default")
      (node (ref "J1") (pin "P$3") (pinfunction "P$3_P$3") (pintype "bidirectional"))
      (node (ref "R12") (pin "2") (pinfunction "2_2") (pintype "passive"))
    )
    (net (code "70") (name "OPBUS") (class "Default")
      (node (ref "R17") (pin "3") (pinfunction "E_3") (pintype "passive"))
      (node (ref "R34") (pin "2") (pinfunction "2_2") (pintype "passive"))
      (node (ref "R35") (pin "3") (pinfunction "E_3") (pintype "passive"))
      (node (ref "R6") (pin "3") (pinfunction "E_3") (pintype "passive"))
      (node (ref "U$1") (pin "ANODE") (pinfunction "A_ANODE") (pintype "passive"))
    )
    (net (code "71") (name "RADBUS") (class "Default")
      (node (ref "R10") (pin "3") (pinfunction "E_3") (pintype "passive"))
      (node (ref "R21") (pin "3") (pinfunction "E_3") (pintype "passive"))
      (node (ref "R33") (pin "2") (pinfunction "2_2") (pintype "passive"))
      (node (ref "R50") (pin "3") (pinfunction "E_3") (pintype "passive"))
      (node (ref "U$2") (pin "ANODE") (pinfunction "A_ANODE") (pintype "passive"))
    )
    (net (code "72") (name "RADIN+") (class "Default")
      (node (ref "C31") (pin "1") (pinfunction "1_1") (pintype "passive"))
      (node (ref "J6") (pin "P$2") (pinfunction "P$2_P$2") (pintype "bidirectional"))
      (node (ref "TR1") (pin "1") (pinfunction "1_1") (pintype "passive"))
    )
    (net (code "73") (name "RADIN-") (class "Default")
      (node (ref "C31") (pin "2") (pinfunction "2_2") (pintype "passive"))
      (node (ref "J6") (pin "P$1") (pinfunction "P$1_P$1") (pintype "bidirectional"))
      (node (ref "J6") (pin "P$4") (pinfunction "P$4_P$4") (pintype "bidirectional"))
      (node (ref "TR1") (pin "3") (pinfunction "3_3") (pintype "passive"))
    )
    (net (code "74") (name "RADMIC+") (class "Default")
      (node (ref "C32") (pin "1") (pinfunction "1_1") (pintype "passive"))
      (node (ref "J3") (pin "P$2") (pinfunction "P$2_P$2") (pintype "bidirectional"))
      (node (ref "TR2") (pin "6") (pinfunction "6_6") (pintype "passive"))
    )
    (net (code "75") (name "RADMIC-") (class "Default")
      (node (ref "C32") (pin "2") (pinfunction "2_2") (pintype "passive"))
      (node (ref "J3") (pin "P$1") (pinfunction "P$1_P$1") (pintype "bidirectional"))
      (node (ref "TR2") (pin "4") (pinfunction "4_4") (pintype "passive"))
    )
    (net (code "76") (name "SPK-OUT") (class "Default")
      (node (ref "C27") (pin "-") (pinfunction "-_-") (pintype "passive"))
      (node (ref "J8") (pin "P$2") (pinfunction "P$2_P$2") (pintype "bidirectional"))
      (node (ref "R44") (pin "2") (pinfunction "2_2") (pintype "passive"))
    )
    (net (code "77") (name "VCC") (class "Default")
      (node (ref "C11") (pin "+") (pinfunction "+_+") (pintype "passive"))
      (node (ref "C12") (pin "1") (pinfunction "1_1") (pintype "passive"))
      (node (ref "C14") (pin "1") (pinfunction "1_1") (pintype "passive"))
      (node (ref "C16") (pin "1") (pinfunction "1_1") (pintype "passive"))
      (node (ref "C22") (pin "1") (pinfunction "1_1") (pintype "passive"))
      (node (ref "C26") (pin "+") (pinfunction "+_+") (pintype "passive"))
      (node (ref "C28") (pin "1") (pinfunction "1_1") (pintype "passive"))
      (node (ref "C9") (pin "1") (pinfunction "1_1") (pintype "passive"))
      (node (ref "IC1") (pin "8") (pinfunction "V+_8") (pintype "power_in"))
      (node (ref "IC10") (pin "6") (pinfunction "VS_6") (pintype "power_in"))
      (node (ref "IC2") (pin "8") (pinfunction "V+_8") (pintype "power_in"))
      (node (ref "IC3") (pin "8") (pinfunction "V+_8") (pintype "power_in"))
      (node (ref "IC4") (pin "8") (pinfunction "V+_8") (pintype "power_in"))
      (node (ref "IC5") (pin "8") (pinfunction "V+_8") (pintype "power_in"))
      (node (ref "IC6") (pin "8") (pinfunction "V+_8") (pintype "power_in"))
      (node (ref "IC7") (pin "8") (pinfunction "V+_8") (pintype "power_in"))
      (node (ref "IC8") (pin "8") (pinfunction "V+_8") (pintype "power_in"))
      (node (ref "R1") (pin "2") (pinfunction "2_2") (pintype "passive"))
      (node (ref "R28") (pin "2") (pinfunction "2_2") (pintype "passive"))
      (node (ref "R41") (pin "2") (pinfunction "2_2") (pintype "passive"))
      (node (ref "R51") (pin "1") (pinfunction "1_1") (pintype "passive"))
      (node (ref "R58") (pin "1") (pinfunction "1_1") (pintype "passive"))
      (node (ref "R64") (pin "1") (pinfunction "1_1") (pintype "passive"))
      (node (ref "U1") (pin "3") (pinfunction "OUT_3") (pintype "passive"))
    )
    (net (code "78") (name "VCC{slash}2") (class "Default")
      (node (ref "C12") (pin "2") (pinfunction "2_2") (pintype "passive"))
      (node (ref "C13") (pin "1") (pinfunction "1_1") (pintype "passive"))
      (node (ref "C14") (pin "2") (pinfunction "2_2") (pintype "passive"))
      (node (ref "C15") (pin "1") (pinfunction "1_1") (pintype "passive"))
      (node (ref "C16") (pin "2") (pinfunction "2_2") (pintype "passive"))
      (node (ref "C2") (pin "2") (pinfunction "2_2") (pintype "passive"))
      (node (ref "C21") (pin "1") (pinfunction "1_1") (pintype "passive"))
      (node (ref "C22") (pin "2") (pinfunction "2_2") (pintype "passive"))
      (node (ref "C23") (pin "1") (pinfunction "1_1") (pintype "passive"))
      (node (ref "C25") (pin "+") (pinfunction "+_+") (pintype "passive"))
      (node (ref "C26") (pin "-") (pinfunction "-_-") (pintype "passive"))
      (node (ref "C28") (pin "2") (pinfunction "2_2") (pintype "passive"))
      (node (ref "C30") (pin "1") (pinfunction "1_1") (pintype "passive"))
      (node (ref "C33") (pin "2") (pinfunction "2_2") (pintype "passive"))
      (node (ref "C34") (pin "2") (pinfunction "2_2") (pintype "passive"))
      (node (ref "C35") (pin "2") (pinfunction "2_2") (pintype "passive"))
      (node (ref "IC1") (pin "1") (pinfunction "OUT_1") (pintype "output"))
      (node (ref "IC1") (pin "2") (pinfunction "-IN_2") (pintype "input"))
      (node (ref "IC1") (pin "6") (pinfunction "-IN_6") (pintype "input"))
      (node (ref "IC1") (pin "7") (pinfunction "OUT_7") (pintype "output"))
      (node (ref "IC2") (pin "3") (pinfunction "+IN_3") (pintype "input"))
      (node (ref "IC3") (pin "3") (pinfunction "+IN_3") (pintype "input"))
      (node (ref "IC5") (pin "5") (pinfunction "+IN_5") (pintype "input"))
      (node (ref "R10") (pin "1") (pinfunction "A_1") (pintype "passive"))
      (node (ref "R17") (pin "1") (pinfunction "A_1") (pintype "passive"))
      (node (ref "R19") (pin "1") (pinfunction "A_1") (pintype "passive"))
      (node (ref "R2") (pin "A") (pinfunction "A_A") (pintype "passive"))
      (node (ref "R21") (pin "1") (pinfunction "A_1") (pintype "passive"))
      (node (ref "R29") (pin "A") (pinfunction "A_A") (pintype "passive"))
      (node (ref "R31") (pin "1") (pinfunction "1_1") (pintype "passive"))
      (node (ref "R32") (pin "A") (pinfunction "A_A") (pintype "passive"))
      (node (ref "R35") (pin "1") (pinfunction "A_1") (pintype "passive"))
      (node (ref "R37") (pin "1") (pinfunction "A_1") (pintype "passive"))
      (node (ref "R4") (pin "1") (pinfunction "1_1") (pintype "passive"))
      (node (ref "R40") (pin "A") (pinfunction "A_A") (pintype "passive"))
      (node (ref "R48") (pin "2") (pinfunction "2_2") (pintype "passive"))
      (node (ref "R50") (pin "1") (pinfunction "A_1") (pintype "passive"))
      (node (ref "R53") (pin "1") (pinfunction "1_1") (pintype "passive"))
      (node (ref "R56") (pin "2") (pinfunction "2_2") (pintype "passive"))
      (node (ref "R59") (pin "1") (pinfunction "1_1") (pintype "passive"))
      (node (ref "R6") (pin "1") (pinfunction "A_1") (pintype "passive"))
      (node (ref "R62") (pin "2") (pinfunction "2_2") (pintype "passive"))
      (node (ref "R65") (pin "1") (pinfunction "1_1") (pintype "passive"))
      (node (ref "R8") (pin "1") (pinfunction "A_1") (pintype "passive"))
      (node (ref "TR1") (pin "4") (pinfunction "4_4") (pintype "passive"))
      (node (ref "TR2") (pin "3") (pinfunction "3_3") (pintype "passive"))
    )
    (net (code "79") (name "VIN") (class "Default")
      (node (ref "J7") (pin "2") (pinfunction "2_2") (pintype "passive"))
      (node (ref "J7") (pin "3") (pinfunction "3_3") (pintype "passive"))
      (node (ref "L1") (pin "1") (pinfunction "1_1") (pintype "passive"))
    )
    (net (code "80") (name "unconnected-(IC10-GAIN-Pad1)") (class "Default")
      (node (ref "IC10") (pin "1") (pinfunction "GAIN_1") (pintype "passive"))
    )
    (net (code "81") (name "unconnected-(IC10-GAIN-Pad8)") (class "Default")
      (node (ref "IC10") (pin "8") (pinfunction "GAIN_8") (pintype "passive"))
    )
    (net (code "82") (name "unconnected-(J1-PadP$4)") (class "Default")
      (node (ref "J1") (pin "P$4") (pinfunction "P$4_P$4") (pintype "bidirectional"))
    )
    (net (code "83") (name "unconnected-(J1-PadP$5)") (class "Default")
      (node (ref "J1") (pin "P$5") (pinfunction "P$5_P$5") (pintype "bidirectional"))
    )
    (net (code "84") (name "unconnected-(J2-PadP$5)") (class "Default")
      (node (ref "J2") (pin "P$5") (pinfunction "P$5_P$5") (pintype "bidirectional"))
    )
    (net (code "85") (name "unconnected-(J3-PadP$3)") (class "Default")
      (node (ref "J3") (pin "P$3") (pinfunction "P$3_P$3") (pintype "bidirectional"))
    )
    (net (code "86") (name "unconnected-(J3-PadP$4)") (class "Default")
      (node (ref "J3") (pin "P$4") (pinfunction "P$4_P$4") (pintype "bidirectional"))
    )
    (net (code "87") (name "unconnected-(J3-PadP$5)") (class "Default")
      (node (ref "J3") (pin "P$5") (pinfunction "P$5_P$5") (pintype "bidirectional"))
    )
    (net (code "88") (name "unconnected-(J4-PadP$4)") (class "Default")
      (node (ref "J4") (pin "P$4") (pinfunction "P$4_P$4") (pintype "bidirectional"))
    )
    (net (code "89") (name "unconnected-(J4-PadP$5)") (class "Default")
      (node (ref "J4") (pin "P$5") (pinfunction "P$5_P$5") (pintype "bidirectional"))
    )
    (net (code "90") (name "unconnected-(J5-PadP$5)") (class "Default")
      (node (ref "J5") (pin "P$5") (pinfunction "P$5_P$5") (pintype "bidirectional"))
    )
    (net (code "91") (name "unconnected-(J6-PadP$3)") (class "Default")
      (node (ref "J6") (pin "P$3") (pinfunction "P$3_P$3") (pintype "bidirectional"))
    )
    (net (code "92") (name "unconnected-(J6-PadP$5)") (class "Default")
      (node (ref "J6") (pin "P$5") (pinfunction "P$5_P$5") (pintype "bidirectional"))
    )
    (net (code "93") (name "unconnected-(J8-PadP$3)") (class "Default")
      (node (ref "J8") (pin "P$3") (pinfunction "P$3_P$3") (pintype "bidirectional"))
    )
    (net (code "94") (name "unconnected-(J8-PadP$4)") (class "Default")
      (node (ref "J8") (pin "P$4") (pinfunction "P$4_P$4") (pintype "bidirectional"))
    )
    (net (code "95") (name "unconnected-(J8-PadP$5)") (class "Default")
      (node (ref "J8") (pin "P$5") (pinfunction "P$5_P$5") (pintype "bidirectional"))
    )
    (net (code "96") (name "unconnected-(TR1-Pad2)") (class "Default")
      (node (ref "TR1") (pin "2") (pinfunction "2_2") (pintype "passive"))
    )
    (net (code "97") (name "unconnected-(TR1-Pad5)") (class "Default")
      (node (ref "TR1") (pin "5") (pinfunction "5_5") (pintype "passive"))
    )
    (net (code "98") (name "unconnected-(TR2-Pad2)") (class "Default")
      (node (ref "TR2") (pin "2") (pinfunction "2_2") (pintype "passive"))
    )
    (net (code "99") (name "unconnected-(TR2-Pad5)") (class "Default")
      (node (ref "TR2") (pin "5") (pinfunction "5_5") (pintype "passive"))
    )
  )
)
